# OPTO_PRESSURE.net
KiCad netlist of a schematic drawn in Altium Designer
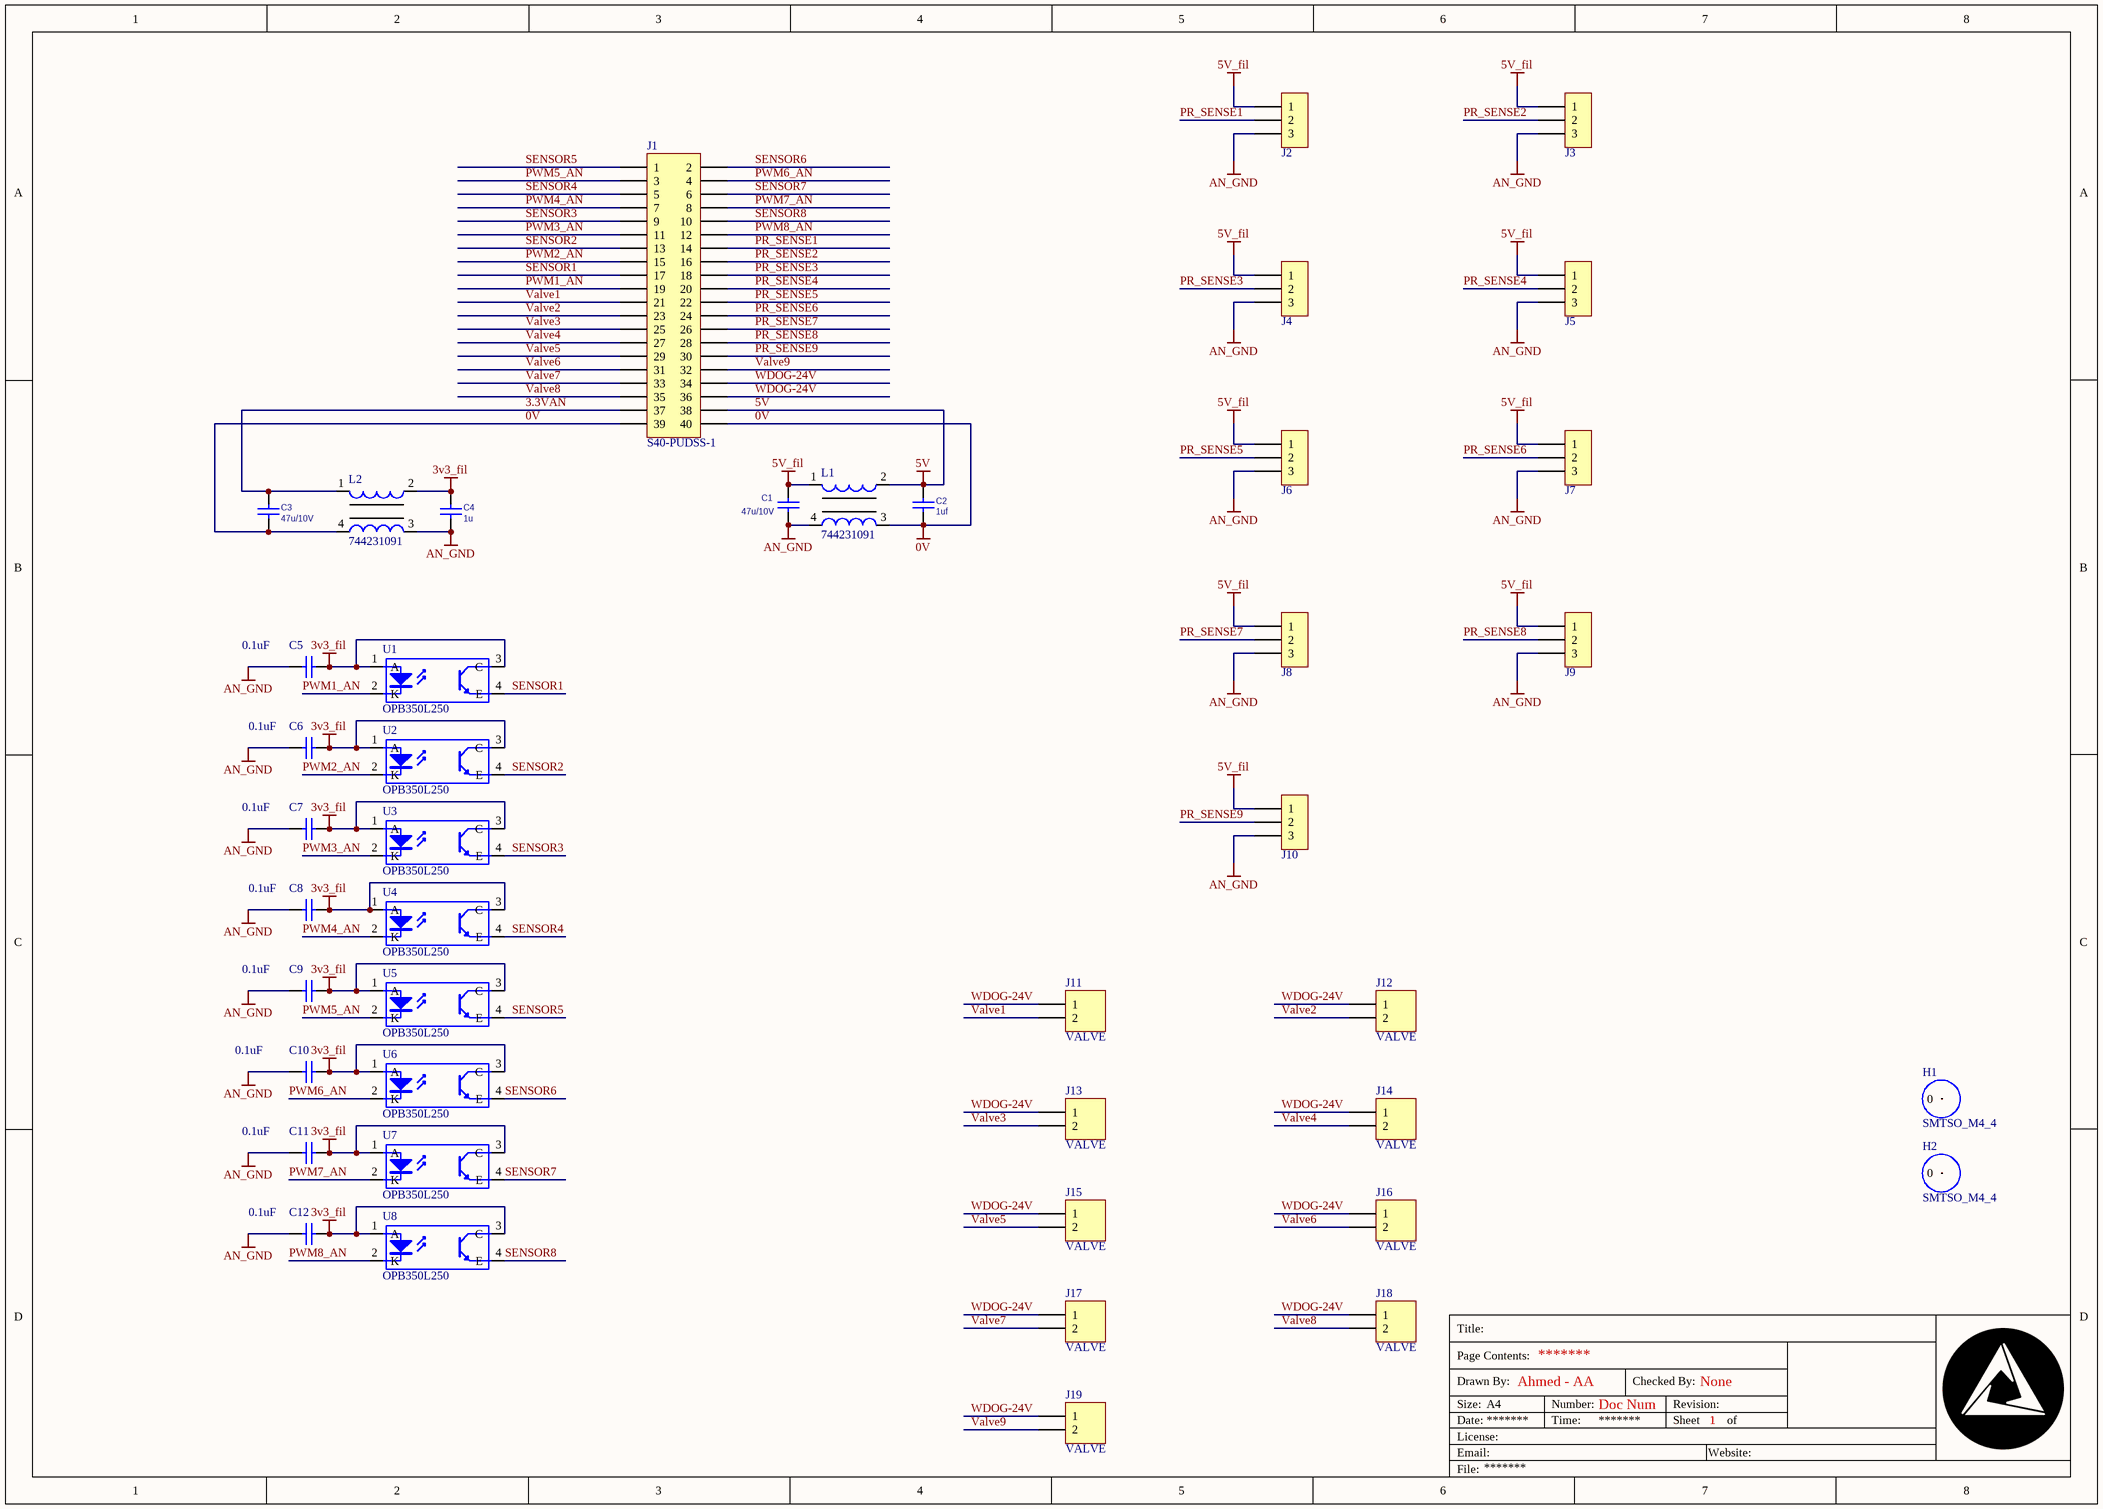
[diagram p0: OPTO_PRESSURE.SchDoc]

(export (version "E")
  (design (tool "Eeschema 10.0.6"))
  (components
    (comp (ref "C1")
      (value "47u/10V")
      (footprint "CAPC2012X13N(0805)")
      (description "Capacitor, Ceramic, 10V, ±20%, X5R, -55°C to 85°C")
      (fields (field (name "02 PART NUMBER") "C2012X5R1A476M125AC"))
      (libsource (lib "pressure_opto") (part "C2012X5R1A476M125AC"))
    )
    (comp (ref "C2")
      (value "1uf")
      (footprint "CAPC1608X09N(0603)")
      (description "Capacitor, Ceramic, 25V, ±10%, X7R, -55°C to 125°C")
      (fields (field (name "02 PART NUMBER") "GRM188R71E105KA12D") (field (name "12 AUTHOR") "D.Grace"))
      (libsource (lib "pressure_opto") (part "GRM188R71E105KA12D"))
    )
    (comp (ref "C3")
      (value "47u/10V")
      (footprint "CAPC2012X13N(0805)")
      (description "Capacitor, Ceramic, 10V, ±20%, X5R, -55°C to 85°C")
      (fields (field (name "02 PART NUMBER") "C2012X5R1A476M125AC"))
      (libsource (lib "pressure_opto") (part "C2012X5R1A476M125AC"))
    )
    (comp (ref "C4")
      (value "1u")
      (footprint "CAPC1608X09N(0603)")
      (description "Capacitor, Ceramic, 25V, ±10%, X7R, -55°C to 125°C")
      (fields (field (name "02 PART NUMBER") "GRM188R71E105KA12D") (field (name "12 AUTHOR") "D.Grace"))
      (libsource (lib "pressure_opto") (part "GRM188R71E105KA12D"))
    )
    (comp (ref "C5")
      (value "0.1uF")
      (footprint "1608[0603]")
      (description "Capacitor (Semiconductor SIM Model)")
      (fields (field (name "Comment") "Cap Semi") (field (name "PUBLISHER") "Altium Limited"))
      (libsource (lib "Miscellaneous Devices") (part "Cap Semi"))
    )
    (comp (ref "C6")
      (value "0.1uF")
      (footprint "1608[0603]")
      (description "Capacitor (Semiconductor SIM Model)")
      (fields (field (name "Comment") "Cap Semi") (field (name "PUBLISHER") "Altium Limited"))
      (libsource (lib "Miscellaneous Devices") (part "Cap Semi"))
    )
    (comp (ref "C7")
      (value "0.1uF")
      (footprint "1608[0603]")
      (description "Capacitor (Semiconductor SIM Model)")
      (fields (field (name "Comment") "Cap Semi") (field (name "PUBLISHER") "Altium Limited"))
      (libsource (lib "Miscellaneous Devices") (part "Cap Semi"))
    )
    (comp (ref "C8")
      (value "0.1uF")
      (footprint "1608[0603]")
      (description "Capacitor (Semiconductor SIM Model)")
      (fields (field (name "Comment") "Cap Semi") (field (name "PUBLISHER") "Altium Limited"))
      (libsource (lib "Miscellaneous Devices") (part "Cap Semi"))
    )
    (comp (ref "C9")
      (value "0.1uF")
      (footprint "1608[0603]")
      (description "Capacitor (Semiconductor SIM Model)")
      (fields (field (name "Comment") "Cap Semi") (field (name "PUBLISHER") "Altium Limited"))
      (libsource (lib "Miscellaneous Devices") (part "Cap Semi"))
    )
    (comp (ref "C10")
      (value "0.1uF")
      (footprint "1608[0603]")
      (description "Capacitor (Semiconductor SIM Model)")
      (fields (field (name "Comment") "Cap Semi") (field (name "PUBLISHER") "Altium Limited"))
      (libsource (lib "Miscellaneous Devices") (part "Cap Semi"))
    )
    (comp (ref "C11")
      (value "0.1uF")
      (footprint "1608[0603]")
      (description "Capacitor (Semiconductor SIM Model)")
      (fields (field (name "Comment") "Cap Semi") (field (name "PUBLISHER") "Altium Limited"))
      (libsource (lib "Miscellaneous Devices") (part "Cap Semi"))
    )
    (comp (ref "C12")
      (value "0.1uF")
      (footprint "1608[0603]")
      (description "Capacitor (Semiconductor SIM Model)")
      (fields (field (name "Comment") "Cap Semi") (field (name "PUBLISHER") "Altium Limited"))
      (libsource (lib "Miscellaneous Devices") (part "Cap Semi"))
    )
    (comp (ref "H1")
      (value "SMTSO_M4_4")
      (footprint "SMTSO_M4_4")
      (description "SMD Standoff M4_4mm")
      (libsource (lib "pressure_opto") (part "SMD standoff"))
    )
    (comp (ref "H2")
      (value "SMTSO_M4_4")
      (footprint "SMTSO_M4_4")
      (description "SMD Standoff M4_4mm")
      (libsource (lib "pressure_opto") (part "SMD standoff"))
    )
    (comp (ref "J1")
      (value "S40-PUDSS-1")
      (footprint "S40B-PUDSS-1")
      (description "Header, 20-Pin, Dual row")
      (fields (field (name "PUBLISHER") "Altium Limited"))
      (libsource (lib "Miscellaneous Connectors") (part "Header 20X2"))
    )
    (comp (ref "J2")
      (value "CON3")
      (footprint "XA3")
      (description "CON")
      (fields (field (name "PART") "Boxed Pin Header 3x1 2.5mm"))
      (libsource (lib "P5_Mainboard") (part "CON3"))
    )
    (comp (ref "J3")
      (value "CON3")
      (footprint "XA3")
      (description "CON")
      (fields (field (name "PART") "Boxed Pin Header 3x1 2.5mm"))
      (libsource (lib "P5_Mainboard") (part "CON3"))
    )
    (comp (ref "J4")
      (value "CON3")
      (footprint "XA3")
      (description "CON")
      (fields (field (name "PART") "Boxed Pin Header 3x1 2.5mm"))
      (libsource (lib "P5_Mainboard") (part "CON3"))
    )
    (comp (ref "J5")
      (value "CON3")
      (footprint "XA3")
      (description "CON")
      (fields (field (name "PART") "Boxed Pin Header 3x1 2.5mm"))
      (libsource (lib "P5_Mainboard") (part "CON3"))
    )
    (comp (ref "J6")
      (value "CON3")
      (footprint "XA3")
      (description "CON")
      (fields (field (name "PART") "Boxed Pin Header 3x1 2.5mm"))
      (libsource (lib "P5_Mainboard") (part "CON3"))
    )
    (comp (ref "J7")
      (value "CON3")
      (footprint "XA3")
      (description "CON")
      (fields (field (name "PART") "Boxed Pin Header 3x1 2.5mm"))
      (libsource (lib "P5_Mainboard") (part "CON3"))
    )
    (comp (ref "J8")
      (value "CON3")
      (footprint "XA3")
      (description "CON")
      (fields (field (name "PART") "Boxed Pin Header 3x1 2.5mm"))
      (libsource (lib "P5_Mainboard") (part "CON3"))
    )
    (comp (ref "J9")
      (value "CON3")
      (footprint "XA3")
      (description "CON")
      (fields (field (name "PART") "Boxed Pin Header 3x1 2.5mm"))
      (libsource (lib "P5_Mainboard") (part "CON3"))
    )
    (comp (ref "J10")
      (value "CON3")
      (footprint "XA3")
      (description "CON")
      (fields (field (name "PART") "Boxed Pin Header 3x1 2.5mm"))
      (libsource (lib "P5_Mainboard") (part "CON3"))
    )
    (comp (ref "J11")
      (value "VALVE")
      (footprint "XA2")
      (description "Header, 2-Pin")
      (fields (field (name "PUBLISHER") "Altium Limited"))
      (libsource (lib "Miscellaneous Connectors") (part "Header 2"))
    )
    (comp (ref "J12")
      (value "VALVE")
      (footprint "XA2")
      (description "Header, 2-Pin")
      (fields (field (name "PUBLISHER") "Altium Limited"))
      (libsource (lib "Miscellaneous Connectors") (part "Header 2"))
    )
    (comp (ref "J13")
      (value "VALVE")
      (footprint "XA2")
      (description "Header, 2-Pin")
      (fields (field (name "PUBLISHER") "Altium Limited"))
      (libsource (lib "Miscellaneous Connectors") (part "Header 2"))
    )
    (comp (ref "J14")
      (value "VALVE")
      (footprint "XA2")
      (description "Header, 2-Pin")
      (fields (field (name "PUBLISHER") "Altium Limited"))
      (libsource (lib "Miscellaneous Connectors") (part "Header 2"))
    )
    (comp (ref "J15")
      (value "VALVE")
      (footprint "XA2")
      (description "Header, 2-Pin")
      (fields (field (name "PUBLISHER") "Altium Limited"))
      (libsource (lib "Miscellaneous Connectors") (part "Header 2"))
    )
    (comp (ref "J16")
      (value "VALVE")
      (footprint "XA2")
      (description "Header, 2-Pin")
      (fields (field (name "PUBLISHER") "Altium Limited"))
      (libsource (lib "Miscellaneous Connectors") (part "Header 2"))
    )
    (comp (ref "J17")
      (value "VALVE")
      (footprint "XA2")
      (description "Header, 2-Pin")
      (fields (field (name "PUBLISHER") "Altium Limited"))
      (libsource (lib "Miscellaneous Connectors") (part "Header 2"))
    )
    (comp (ref "J18")
      (value "VALVE")
      (footprint "XA2")
      (description "Header, 2-Pin")
      (fields (field (name "PUBLISHER") "Altium Limited"))
      (libsource (lib "Miscellaneous Connectors") (part "Header 2"))
    )
    (comp (ref "J19")
      (value "VALVE")
      (footprint "XA2")
      (description "Header, 2-Pin")
      (fields (field (name "PUBLISHER") "Altium Limited"))
      (libsource (lib "Miscellaneous Connectors") (part "Header 2"))
    )
    (comp (ref "L1")
      (value "744231091")
      (footprint "WE-CNSW-0805")
      (description "SMD Common Mode Noise Suppressor WE-CNSW, Z = 90 Ohm")
      (libsource (lib "Altium Content Vault") (part "CMP-0222-00046-1"))
    )
    (comp (ref "L2")
      (value "744231091")
      (footprint "WE-CNSW-0805")
      (description "SMD Common Mode Noise Suppressor WE-CNSW, Z = 90 Ohm")
      (libsource (lib "Altium Content Vault") (part "CMP-0222-00046-1"))
    )
    (comp (ref "U1")
      (value "OPB350L250")
      (footprint "OPB350L250")
      (description "4-Pin Phototransistor Optocoupler")
      (fields (field (name "PUBLISHER") "Altium Limited"))
      (libsource (lib "pressure_opto") (part "Optoisolator1"))
    )
    (comp (ref "U2")
      (value "OPB350L250")
      (footprint "OPB350L250")
      (description "4-Pin Phototransistor Optocoupler")
      (fields (field (name "PUBLISHER") "Altium Limited"))
      (libsource (lib "pressure_opto") (part "Optoisolator1"))
    )
    (comp (ref "U3")
      (value "OPB350L250")
      (footprint "OPB350L250")
      (description "4-Pin Phototransistor Optocoupler")
      (fields (field (name "PUBLISHER") "Altium Limited"))
      (libsource (lib "pressure_opto") (part "Optoisolator1"))
    )
    (comp (ref "U4")
      (value "OPB350L250")
      (footprint "OPB350L250")
      (description "4-Pin Phototransistor Optocoupler")
      (fields (field (name "PUBLISHER") "Altium Limited"))
      (libsource (lib "pressure_opto") (part "Optoisolator1"))
    )
    (comp (ref "U5")
      (value "OPB350L250")
      (footprint "OPB350L250")
      (description "4-Pin Phototransistor Optocoupler")
      (fields (field (name "PUBLISHER") "Altium Limited"))
      (libsource (lib "pressure_opto") (part "Optoisolator1"))
    )
    (comp (ref "U6")
      (value "OPB350L250")
      (footprint "OPB350L250")
      (description "4-Pin Phototransistor Optocoupler")
      (fields (field (name "PUBLISHER") "Altium Limited"))
      (libsource (lib "pressure_opto") (part "Optoisolator1"))
    )
    (comp (ref "U7")
      (value "OPB350L250")
      (footprint "OPB350L250")
      (description "4-Pin Phototransistor Optocoupler")
      (fields (field (name "PUBLISHER") "Altium Limited"))
      (libsource (lib "pressure_opto") (part "Optoisolator1"))
    )
    (comp (ref "U8")
      (value "OPB350L250")
      (footprint "OPB350L250")
      (description "4-Pin Phototransistor Optocoupler")
      (fields (field (name "PUBLISHER") "Altium Limited"))
      (libsource (lib "pressure_opto") (part "Optoisolator1"))
    )
  )
  (nets
    (net (code "1") (name "/3.3VAN") (class "Default")
      (node (ref "C3") (pin "2") (pinfunction "2_2") (pintype "passive"))
      (node (ref "J1") (pin "37") (pinfunction "37_37") (pintype "passive"))
      (node (ref "L2") (pin "1") (pinfunction "1_1") (pintype "passive"))
    )
    (net (code "2") (name "/PR_SENSE1") (class "Default")
      (node (ref "J1") (pin "14") (pinfunction "14_14") (pintype "passive"))
      (node (ref "J2") (pin "2") (pinfunction "2_2") (pintype "passive"))
    )
    (net (code "3") (name "/PR_SENSE2") (class "Default")
      (node (ref "J1") (pin "16") (pinfunction "16_16") (pintype "passive"))
      (node (ref "J3") (pin "2") (pinfunction "2_2") (pintype "passive"))
    )
    (net (code "4") (name "/PR_SENSE3") (class "Default")
      (node (ref "J1") (pin "18") (pinfunction "18_18") (pintype "passive"))
      (node (ref "J4") (pin "2") (pinfunction "2_2") (pintype "passive"))
    )
    (net (code "5") (name "/PR_SENSE4") (class "Default")
      (node (ref "J1") (pin "20") (pinfunction "20_20") (pintype "passive"))
      (node (ref "J5") (pin "2") (pinfunction "2_2") (pintype "passive"))
    )
    (net (code "6") (name "/PR_SENSE5") (class "Default")
      (node (ref "J1") (pin "22") (pinfunction "22_22") (pintype "passive"))
      (node (ref "J6") (pin "2") (pinfunction "2_2") (pintype "passive"))
    )
    (net (code "7") (name "/PR_SENSE6") (class "Default")
      (node (ref "J1") (pin "24") (pinfunction "24_24") (pintype "passive"))
      (node (ref "J7") (pin "2") (pinfunction "2_2") (pintype "passive"))
    )
    (net (code "8") (name "/PR_SENSE7") (class "Default")
      (node (ref "J1") (pin "26") (pinfunction "26_26") (pintype "passive"))
      (node (ref "J8") (pin "2") (pinfunction "2_2") (pintype "passive"))
    )
    (net (code "9") (name "/PR_SENSE8") (class "Default")
      (node (ref "J1") (pin "28") (pinfunction "28_28") (pintype "passive"))
      (node (ref "J9") (pin "2") (pinfunction "2_2") (pintype "passive"))
    )
    (net (code "10") (name "/PR_SENSE9") (class "Default")
      (node (ref "J1") (pin "30") (pinfunction "30_30") (pintype "passive"))
      (node (ref "J10") (pin "2") (pinfunction "2_2") (pintype "passive"))
    )
    (net (code "11") (name "/PWM1_AN") (class "Default")
      (node (ref "J1") (pin "19") (pinfunction "19_19") (pintype "passive"))
      (node (ref "U1") (pin "2") (pinfunction "K_2") (pintype "passive"))
    )
    (net (code "12") (name "/PWM2_AN") (class "Default")
      (node (ref "J1") (pin "15") (pinfunction "15_15") (pintype "passive"))
      (node (ref "U2") (pin "2") (pinfunction "K_2") (pintype "passive"))
    )
    (net (code "13") (name "/PWM3_AN") (class "Default")
      (node (ref "J1") (pin "11") (pinfunction "11_11") (pintype "passive"))
      (node (ref "U3") (pin "2") (pinfunction "K_2") (pintype "passive"))
    )
    (net (code "14") (name "/PWM4_AN") (class "Default")
      (node (ref "J1") (pin "7") (pinfunction "7_7") (pintype "passive"))
      (node (ref "U4") (pin "2") (pinfunction "K_2") (pintype "passive"))
    )
    (net (code "15") (name "/PWM5_AN") (class "Default")
      (node (ref "J1") (pin "3") (pinfunction "3_3") (pintype "passive"))
      (node (ref "U5") (pin "2") (pinfunction "K_2") (pintype "passive"))
    )
    (net (code "16") (name "/PWM6_AN") (class "Default")
      (node (ref "J1") (pin "4") (pinfunction "4_4") (pintype "passive"))
      (node (ref "U6") (pin "2") (pinfunction "K_2") (pintype "passive"))
    )
    (net (code "17") (name "/PWM7_AN") (class "Default")
      (node (ref "J1") (pin "8") (pinfunction "8_8") (pintype "passive"))
      (node (ref "U7") (pin "2") (pinfunction "K_2") (pintype "passive"))
    )
    (net (code "18") (name "/PWM8_AN") (class "Default")
      (node (ref "J1") (pin "12") (pinfunction "12_12") (pintype "passive"))
      (node (ref "U8") (pin "2") (pinfunction "K_2") (pintype "passive"))
    )
    (net (code "19") (name "/SENSOR1") (class "Default")
      (node (ref "J1") (pin "17") (pinfunction "17_17") (pintype "passive"))
      (node (ref "U1") (pin "4") (pinfunction "E_4") (pintype "passive"))
    )
    (net (code "20") (name "/SENSOR2") (class "Default")
      (node (ref "J1") (pin "13") (pinfunction "13_13") (pintype "passive"))
      (node (ref "U2") (pin "4") (pinfunction "E_4") (pintype "passive"))
    )
    (net (code "21") (name "/SENSOR3") (class "Default")
      (node (ref "J1") (pin "9") (pinfunction "9_9") (pintype "passive"))
      (node (ref "U3") (pin "4") (pinfunction "E_4") (pintype "passive"))
    )
    (net (code "22") (name "/SENSOR4") (class "Default")
      (node (ref "J1") (pin "5") (pinfunction "5_5") (pintype "passive"))
      (node (ref "U4") (pin "4") (pinfunction "E_4") (pintype "passive"))
    )
    (net (code "23") (name "/SENSOR5") (class "Default")
      (node (ref "J1") (pin "1") (pinfunction "1_1") (pintype "passive"))
      (node (ref "U5") (pin "4") (pinfunction "E_4") (pintype "passive"))
    )
    (net (code "24") (name "/SENSOR6") (class "Default")
      (node (ref "J1") (pin "2") (pinfunction "2_2") (pintype "passive"))
      (node (ref "U6") (pin "4") (pinfunction "E_4") (pintype "passive"))
    )
    (net (code "25") (name "/SENSOR7") (class "Default")
      (node (ref "J1") (pin "6") (pinfunction "6_6") (pintype "passive"))
      (node (ref "U7") (pin "4") (pinfunction "E_4") (pintype "passive"))
    )
    (net (code "26") (name "/SENSOR8") (class "Default")
      (node (ref "J1") (pin "10") (pinfunction "10_10") (pintype "passive"))
      (node (ref "U8") (pin "4") (pinfunction "E_4") (pintype "passive"))
    )
    (net (code "27") (name "/Valve1") (class "Default")
      (node (ref "J1") (pin "21") (pinfunction "21_21") (pintype "passive"))
      (node (ref "J11") (pin "2") (pinfunction "2_2") (pintype "passive"))
    )
    (net (code "28") (name "/Valve2") (class "Default")
      (node (ref "J1") (pin "23") (pinfunction "23_23") (pintype "passive"))
      (node (ref "J12") (pin "2") (pinfunction "2_2") (pintype "passive"))
    )
    (net (code "29") (name "/Valve3") (class "Default")
      (node (ref "J1") (pin "25") (pinfunction "25_25") (pintype "passive"))
      (node (ref "J13") (pin "2") (pinfunction "2_2") (pintype "passive"))
    )
    (net (code "30") (name "/Valve4") (class "Default")
      (node (ref "J1") (pin "27") (pinfunction "27_27") (pintype "passive"))
      (node (ref "J14") (pin "2") (pinfunction "2_2") (pintype "passive"))
    )
    (net (code "31") (name "/Valve5") (class "Default")
      (node (ref "J1") (pin "29") (pinfunction "29_29") (pintype "passive"))
      (node (ref "J15") (pin "2") (pinfunction "2_2") (pintype "passive"))
    )
    (net (code "32") (name "/Valve6") (class "Default")
      (node (ref "J1") (pin "31") (pinfunction "31_31") (pintype "passive"))
      (node (ref "J16") (pin "2") (pinfunction "2_2") (pintype "passive"))
    )
    (net (code "33") (name "/Valve7") (class "Default")
      (node (ref "J1") (pin "33") (pinfunction "33_33") (pintype "passive"))
      (node (ref "J17") (pin "2") (pinfunction "2_2") (pintype "passive"))
    )
    (net (code "34") (name "/Valve8") (class "Default")
      (node (ref "J1") (pin "35") (pinfunction "35_35") (pintype "passive"))
      (node (ref "J18") (pin "2") (pinfunction "2_2") (pintype "passive"))
    )
    (net (code "35") (name "/Valve9") (class "Default")
      (node (ref "J1") (pin "32") (pinfunction "32_32") (pintype "passive"))
      (node (ref "J19") (pin "2") (pinfunction "2_2") (pintype "passive"))
    )
    (net (code "36") (name "/WDOG-24V") (class "Default")
      (node (ref "J1") (pin "34") (pinfunction "34_34") (pintype "passive"))
      (node (ref "J1") (pin "36") (pinfunction "36_36") (pintype "passive"))
      (node (ref "J11") (pin "1") (pinfunction "1_1") (pintype "passive"))
      (node (ref "J12") (pin "1") (pinfunction "1_1") (pintype "passive"))
      (node (ref "J13") (pin "1") (pinfunction "1_1") (pintype "passive"))
      (node (ref "J14") (pin "1") (pinfunction "1_1") (pintype "passive"))
      (node (ref "J15") (pin "1") (pinfunction "1_1") (pintype "passive"))
      (node (ref "J16") (pin "1") (pinfunction "1_1") (pintype "passive"))
      (node (ref "J17") (pin "1") (pinfunction "1_1") (pintype "passive"))
      (node (ref "J18") (pin "1") (pinfunction "1_1") (pintype "passive"))
      (node (ref "J19") (pin "1") (pinfunction "1_1") (pintype "passive"))
    )
    (net (code "37") (name "0V") (class "Default")
      (node (ref "C2") (pin "1") (pinfunction "1_1") (pintype "passive"))
      (node (ref "C3") (pin "1") (pinfunction "1_1") (pintype "passive"))
      (node (ref "J1") (pin "39") (pinfunction "39_39") (pintype "passive"))
      (node (ref "J1") (pin "40") (pinfunction "40_40") (pintype "passive"))
      (node (ref "L1") (pin "3") (pinfunction "3_3") (pintype "passive"))
      (node (ref "L2") (pin "4") (pinfunction "4_4") (pintype "passive"))
    )
    (net (code "38") (name "3v3_fil") (class "Default")
      (node (ref "C10") (pin "1") (pinfunction "1_1") (pintype "passive"))
      (node (ref "C11") (pin "1") (pinfunction "1_1") (pintype "passive"))
      (node (ref "C12") (pin "1") (pinfunction "1_1") (pintype "passive"))
      (node (ref "C4") (pin "2") (pinfunction "2_2") (pintype "passive"))
      (node (ref "C5") (pin "1") (pinfunction "1_1") (pintype "passive"))
      (node (ref "C6") (pin "1") (pinfunction "1_1") (pintype "passive"))
      (node (ref "C7") (pin "1") (pinfunction "1_1") (pintype "passive"))
      (node (ref "C8") (pin "1") (pinfunction "1_1") (pintype "passive"))
      (node (ref "C9") (pin "1") (pinfunction "1_1") (pintype "passive"))
      (node (ref "L2") (pin "2") (pinfunction "2_2") (pintype "passive"))
      (node (ref "U1") (pin "1") (pinfunction "A_1") (pintype "passive"))
      (node (ref "U1") (pin "3") (pinfunction "C_3") (pintype "passive"))
      (node (ref "U2") (pin "1") (pinfunction "A_1") (pintype "passive"))
      (node (ref "U2") (pin "3") (pinfunction "C_3") (pintype "passive"))
      (node (ref "U3") (pin "1") (pinfunction "A_1") (pintype "passive"))
      (node (ref "U3") (pin "3") (pinfunction "C_3") (pintype "passive"))
      (node (ref "U4") (pin "1") (pinfunction "A_1") (pintype "passive"))
      (node (ref "U4") (pin "3") (pinfunction "C_3") (pintype "passive"))
      (node (ref "U5") (pin "1") (pinfunction "A_1") (pintype "passive"))
      (node (ref "U5") (pin "3") (pinfunction "C_3") (pintype "passive"))
      (node (ref "U6") (pin "1") (pinfunction "A_1") (pintype "passive"))
      (node (ref "U6") (pin "3") (pinfunction "C_3") (pintype "passive"))
      (node (ref "U7") (pin "1") (pinfunction "A_1") (pintype "passive"))
      (node (ref "U7") (pin "3") (pinfunction "C_3") (pintype "passive"))
      (node (ref "U8") (pin "1") (pinfunction "A_1") (pintype "passive"))
      (node (ref "U8") (pin "3") (pinfunction "C_3") (pintype "passive"))
    )
    (net (code "39") (name "5V") (class "Default")
      (node (ref "C2") (pin "2") (pinfunction "2_2") (pintype "passive"))
      (node (ref "J1") (pin "38") (pinfunction "38_38") (pintype "passive"))
      (node (ref "L1") (pin "2") (pinfunction "2_2") (pintype "passive"))
    )
    (net (code "40") (name "5V_fil") (class "Default")
      (node (ref "C1") (pin "2") (pinfunction "2_2") (pintype "passive"))
      (node (ref "J10") (pin "1") (pinfunction "1_1") (pintype "passive"))
      (node (ref "J2") (pin "1") (pinfunction "1_1") (pintype "passive"))
      (node (ref "J3") (pin "1") (pinfunction "1_1") (pintype "passive"))
      (node (ref "J4") (pin "1") (pinfunction "1_1") (pintype "passive"))
      (node (ref "J5") (pin "1") (pinfunction "1_1") (pintype "passive"))
      (node (ref "J6") (pin "1") (pinfunction "1_1") (pintype "passive"))
      (node (ref "J7") (pin "1") (pinfunction "1_1") (pintype "passive"))
      (node (ref "J8") (pin "1") (pinfunction "1_1") (pintype "passive"))
      (node (ref "J9") (pin "1") (pinfunction "1_1") (pintype "passive"))
      (node (ref "L1") (pin "1") (pinfunction "1_1") (pintype "passive"))
    )
    (net (code "41") (name "AN_GND") (class "Default")
      (node (ref "C1") (pin "1") (pinfunction "1_1") (pintype "passive"))
      (node (ref "C10") (pin "2") (pinfunction "2_2") (pintype "passive"))
      (node (ref "C11") (pin "2") (pinfunction "2_2") (pintype "passive"))
      (node (ref "C12") (pin "2") (pinfunction "2_2") (pintype "passive"))
      (node (ref "C4") (pin "1") (pinfunction "1_1") (pintype "passive"))
      (node (ref "C5") (pin "2") (pinfunction "2_2") (pintype "passive"))
      (node (ref "C6") (pin "2") (pinfunction "2_2") (pintype "passive"))
      (node (ref "C7") (pin "2") (pinfunction "2_2") (pintype "passive"))
      (node (ref "C8") (pin "2") (pinfunction "2_2") (pintype "passive"))
      (node (ref "C9") (pin "2") (pinfunction "2_2") (pintype "passive"))
      (node (ref "J10") (pin "3") (pinfunction "3_3") (pintype "passive"))
      (node (ref "J2") (pin "3") (pinfunction "3_3") (pintype "passive"))
      (node (ref "J3") (pin "3") (pinfunction "3_3") (pintype "passive"))
      (node (ref "J4") (pin "3") (pinfunction "3_3") (pintype "passive"))
      (node (ref "J5") (pin "3") (pinfunction "3_3") (pintype "passive"))
      (node (ref "J6") (pin "3") (pinfunction "3_3") (pintype "passive"))
      (node (ref "J7") (pin "3") (pinfunction "3_3") (pintype "passive"))
      (node (ref "J8") (pin "3") (pinfunction "3_3") (pintype "passive"))
      (node (ref "J9") (pin "3") (pinfunction "3_3") (pintype "passive"))
      (node (ref "L1") (pin "4") (pinfunction "4_4") (pintype "passive"))
      (node (ref "L2") (pin "3") (pinfunction "3_3") (pintype "passive"))
    )
    (net (code "42") (name "unconnected-(H1-0-Pad)") (class "Default")
      (node (ref "H1") (pin "") (pinfunction "0_") (pintype "passive"))
    )
    (net (code "43") (name "unconnected-(H2-0-Pad)") (class "Default")
      (node (ref "H2") (pin "") (pinfunction "0_") (pintype "passive"))
    )
  )
)
